# Sch_mppt_board.net
KiCad netlist of a schematic drawn in Altium Designer
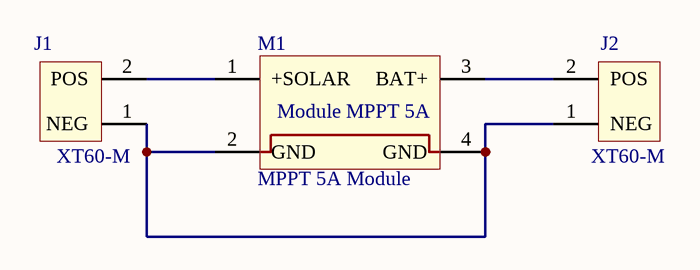
[diagram p0: Sch_mppt_board.SchDoc]

(export (version "E")
  (design (tool "Eeschema 10.0.6"))
  (components
    (comp (ref "J1")
      (value "XT60-M")
      (footprint "XT60-M")
      (fields (field (name "MF") "AMASS"))
      (libsource (lib "") (part "XT60-M_1"))
    )
    (comp (ref "J2")
      (value "XT60-M")
      (footprint "XT60-M")
      (fields (field (name "MF") "AMASS"))
      (libsource (lib "alib_pnphien") (part "XT60-M"))
    )
    (comp (ref "M1")
      (value "MPPT 5A Module")
      (footprint "MODULE MPPT 5A BQ24650")
      (description "Module Solar Charge MPPT 5A")
      (libsource (lib "alib_pnphien") (part "Module BQ24650 MPPT 5A"))
    )
  )
  (nets
    (net (code "1") (name "Net-(J1-NEG)") (class "Default")
      (node (ref "J1") (pin "1") (pinfunction "NEG_1") (pintype "passive"))
      (node (ref "J2") (pin "1") (pinfunction "NEG_1") (pintype "passive"))
      (node (ref "M1") (pin "2") (pinfunction "GND_2") (pintype "passive"))
      (node (ref "M1") (pin "4") (pinfunction "GND_4") (pintype "passive"))
    )
    (net (code "2") (name "Net-(J1-POS)") (class "Default")
      (node (ref "J1") (pin "2") (pinfunction "POS_2") (pintype "passive"))
      (node (ref "M1") (pin "1") (pinfunction "+SOLAR_1") (pintype "passive"))
    )
    (net (code "3") (name "Net-(J2-POS)") (class "Default")
      (node (ref "J2") (pin "2") (pinfunction "POS_2") (pintype "passive"))
      (node (ref "M1") (pin "3") (pinfunction "BAT+_3") (pintype "passive"))
    )
  )
)
